# DIY_OpenEVSE_Arduino_Shield.net
KiCad netlist of a schematic drawn in EAGLE
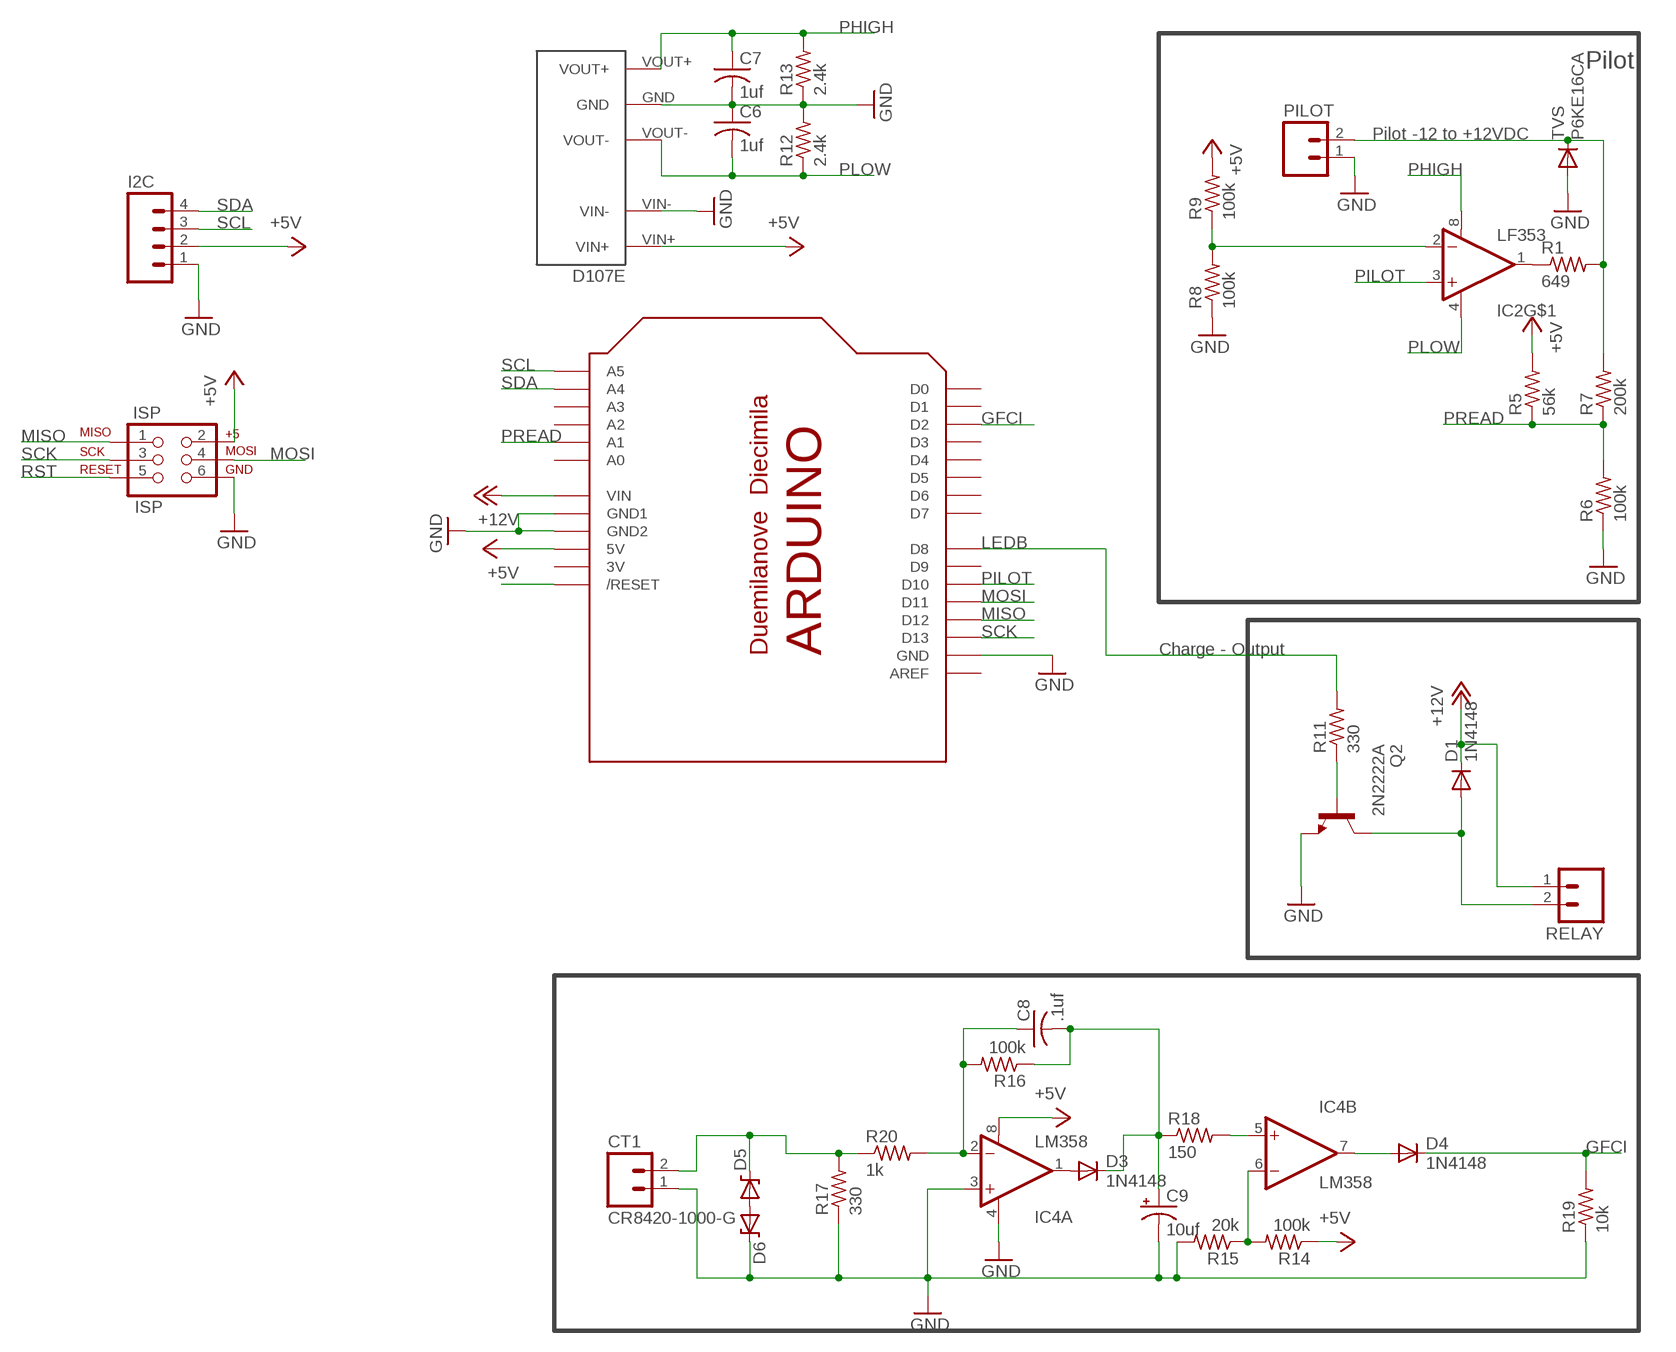
[diagram p0: schematic, sheet 1]

(export (version "E")
  (design (tool "Eeschema 10.0.6"))
  (components
    (comp (ref "C6")
      (value "1uf")
      (footprint "eagle-import:C025-024X044")
      (libsource (lib "eagle-import") (part "C-US025-024X044"))
    )
    (comp (ref "C7")
      (value "1uf")
      (footprint "eagle-import:C025-024X044")
      (libsource (lib "eagle-import") (part "C-US025-024X044"))
    )
    (comp (ref "C8")
      (value ".1uf")
      (footprint "eagle-import:C025-024X044")
      (libsource (lib "eagle-import") (part "C-US025-024X044"))
    )
    (comp (ref "C9")
      (value "10uf")
      (footprint "eagle-import:CPOL-RADIAL-10UF-25V")
      (libsource (lib "eagle-import") (part "CAP_POLPTH2"))
    )
    (comp (ref "CT1")
      (value "CR8420-1000-G")
      (footprint "eagle-import:1X02_LOCK")
      (libsource (lib "eagle-import") (part "M02LOCK"))
    )
    (comp (ref "D1")
      (value "1N4148")
      (footprint "eagle-import:DIODE-1N4148")
      (libsource (lib "eagle-import") (part "DIODE1N4148"))
    )
    (comp (ref "D3")
      (value "1N4148")
      (footprint "eagle-import:DIODE-1N4148")
      (libsource (lib "eagle-import") (part "DIODE1N4148"))
    )
    (comp (ref "D4")
      (value "1N4148")
      (footprint "eagle-import:DIODE-1N4148")
      (libsource (lib "eagle-import") (part "DIODE1N4148"))
    )
    (comp (ref "D5")
      (value "DIODE-ZENERPTH")
      (footprint "eagle-import:DIODE-ZENER")
      (libsource (lib "eagle-import") (part "DIODE-ZENERPTH"))
    )
    (comp (ref "D6")
      (value "DIODE-ZENERPTH")
      (footprint "eagle-import:DIODE-ZENER")
      (libsource (lib "eagle-import") (part "DIODE-ZENERPTH"))
    )
    (comp (ref "I2C")
      (value "M04LOCK")
      (footprint "eagle-import:1X04_LOCK")
      (libsource (lib "eagle-import") (part "M04LOCK"))
    )
    (comp (ref "IC2")
      (value "LF353")
      (footprint "eagle-import:DIP08")
      (libsource (lib "eagle-import") (part "LM358"))
    )
    (comp (ref "IC4")
      (value "LM358")
      (footprint "eagle-import:DIP08")
      (libsource (lib "eagle-import") (part "OPAMP-DUALDIP"))
    )
    (comp (ref "ISP")
      (value "ISP")
      (footprint "eagle-import:2X3_LOCK")
      (libsource (lib "eagle-import") (part "AVR_SPI_PRG_62X3_LOCK"))
    )
    (comp (ref "PILOT")
      (value "M025MM")
      (footprint "eagle-import:SCREWTERMINAL-5MM-2")
      (libsource (lib "eagle-import") (part "M025MM"))
    )
    (comp (ref "Q2")
      (value "2N2222A")
      (footprint "eagle-import:TO18")
      (libsource (lib "eagle-import") (part "2N2222A"))
    )
    (comp (ref "R1")
      (value "649")
      (footprint "eagle-import:0204_7")
      (libsource (lib "eagle-import") (part "R-US_0204/7"))
    )
    (comp (ref "R5")
      (value "56k")
      (footprint "eagle-import:0204_7")
      (libsource (lib "eagle-import") (part "R-US_0204/7"))
    )
    (comp (ref "R6")
      (value "100k")
      (footprint "eagle-import:0204_7")
      (libsource (lib "eagle-import") (part "R-US_0204/7"))
    )
    (comp (ref "R7")
      (value "200k")
      (footprint "eagle-import:0204_7")
      (libsource (lib "eagle-import") (part "R-US_0204/7"))
    )
    (comp (ref "R8")
      (value "100k")
      (footprint "eagle-import:0204_7")
      (libsource (lib "eagle-import") (part "R-US_0204/7"))
    )
    (comp (ref "R9")
      (value "100k")
      (footprint "eagle-import:0204_7")
      (libsource (lib "eagle-import") (part "R-US_0204/7"))
    )
    (comp (ref "R11")
      (value "330")
      (footprint "eagle-import:0204_7")
      (libsource (lib "eagle-import") (part "R-US_0204/7"))
    )
    (comp (ref "R12")
      (value "2.4k")
      (footprint "eagle-import:0204_7")
      (libsource (lib "eagle-import") (part "R-US_0204/7"))
    )
    (comp (ref "R13")
      (value "2.4k")
      (footprint "eagle-import:0204_7")
      (libsource (lib "eagle-import") (part "R-US_0204/7"))
    )
    (comp (ref "R14")
      (value "100k")
      (footprint "eagle-import:0204_7")
      (libsource (lib "eagle-import") (part "R-US_0204/7"))
    )
    (comp (ref "R15")
      (value "20k")
      (footprint "eagle-import:0204_7")
      (libsource (lib "eagle-import") (part "R-US_0204/7"))
    )
    (comp (ref "R16")
      (value "100k")
      (footprint "eagle-import:0204_7")
      (libsource (lib "eagle-import") (part "R-US_0204/7"))
    )
    (comp (ref "R17")
      (value "330")
      (footprint "eagle-import:0204_7")
      (libsource (lib "eagle-import") (part "R-US_0204/7"))
    )
    (comp (ref "R18")
      (value "150")
      (footprint "eagle-import:0204_7")
      (libsource (lib "eagle-import") (part "R-US_0204/7"))
    )
    (comp (ref "R19")
      (value "10k")
      (footprint "eagle-import:0204_7")
      (libsource (lib "eagle-import") (part "R-US_0204/7"))
    )
    (comp (ref "R20")
      (value "1k")
      (footprint "eagle-import:0204_7")
      (libsource (lib "eagle-import") (part "R-US_0204/7"))
    )
    (comp (ref "RELAY")
      (value "M023.5MM_LOCK")
      (footprint "eagle-import:SCREWTERMINAL-3.5MM-2_LOCK")
      (libsource (lib "eagle-import") (part "M023.5MM_LOCK"))
    )
    (comp (ref "TVS")
      (value "P6KE16CA")
      (footprint "eagle-import:DIODE-1N4001")
      (libsource (lib "eagle-import") (part "DIODEPTH"))
    )
    (comp (ref "U$1")
      (value "DCDC_SIP")
      (footprint "eagle-import:DCDC_SIP")
      (libsource (lib "eagle-import") (part "DCDC_SIP"))
    )
    (comp (ref "U$2")
      (value "ARDUINOUNO")
      (footprint "eagle-import:ARDUINO")
      (libsource (lib "eagle-import") (part "ARDUINOUNO"))
    )
  )
  (nets
    (net (code "1") (name "+5V") (class "Default")
      (node (ref "I2C") (pin "2") (pinfunction "2_2") (pintype "passive"))
      (node (ref "IC4") (pin "8") (pinfunction "V+_8") (pintype "power_in"))
      (node (ref "ISP") (pin "2") (pinfunction "2_2") (pintype "passive"))
      (node (ref "R14") (pin "1") (pinfunction "1_1") (pintype "passive"))
      (node (ref "R5") (pin "2") (pinfunction "2_2") (pintype "passive"))
      (node (ref "R9") (pin "2") (pinfunction "2_2") (pintype "passive"))
      (node (ref "U$1") (pin "VIN+") (pinfunction "VIN+_VIN+") (pintype "bidirectional"))
      (node (ref "U$2") (pin "5V") (pinfunction "5V_5V") (pintype "power_in"))
    )
    (net (code "2") (name "+12V") (class "Default")
      (node (ref "D1") (pin "C") (pinfunction "C_C") (pintype "passive"))
      (node (ref "RELAY") (pin "1") (pinfunction "1_1") (pintype "passive"))
      (node (ref "U$2") (pin "VIN") (pinfunction "VIN_VIN") (pintype "power_in"))
    )
    (net (code "3") (name "/3V") (class "Default")
      (node (ref "U$2") (pin "3V") (pinfunction "3V_3V") (pintype "power_in"))
    )
    (net (code "4") (name "/GFCI") (class "Default")
      (node (ref "D4") (pin "C") (pinfunction "C_C") (pintype "passive"))
      (node (ref "R19") (pin "2") (pinfunction "2_2") (pintype "passive"))
      (node (ref "U$2") (pin "D2") (pinfunction "D2_D2") (pintype "bidirectional"))
    )
    (net (code "5") (name "/LEDB") (class "Default")
      (node (ref "R11") (pin "2") (pinfunction "2_2") (pintype "passive"))
      (node (ref "U$2") (pin "D8") (pinfunction "D8_D8") (pintype "bidirectional"))
    )
    (net (code "6") (name "/MISO") (class "Default")
      (node (ref "ISP") (pin "1") (pinfunction "1_1") (pintype "passive"))
      (node (ref "U$2") (pin "D12") (pinfunction "D12_D12") (pintype "bidirectional"))
    )
    (net (code "7") (name "/MOSI") (class "Default")
      (node (ref "ISP") (pin "4") (pinfunction "4_4") (pintype "passive"))
      (node (ref "U$2") (pin "D11") (pinfunction "D11_D11") (pintype "bidirectional"))
    )
    (net (code "8") (name "/PHIGH") (class "Default")
      (node (ref "C7") (pin "1") (pinfunction "1_1") (pintype "passive"))
      (node (ref "IC2") (pin "8") (pinfunction "V+_8") (pintype "power_in"))
      (node (ref "R13") (pin "2") (pinfunction "2_2") (pintype "passive"))
      (node (ref "U$1") (pin "VOUT+") (pinfunction "VOUT+_VOUT+") (pintype "bidirectional"))
    )
    (net (code "9") (name "/PILOT") (class "Default")
      (node (ref "IC2") (pin "3") (pinfunction "+IN_3") (pintype "input"))
      (node (ref "U$2") (pin "D10") (pinfunction "D10_D10") (pintype "bidirectional"))
    )
    (net (code "10") (name "/PLOW") (class "Default")
      (node (ref "C6") (pin "2") (pinfunction "2_2") (pintype "passive"))
      (node (ref "IC2") (pin "4") (pinfunction "V-_4") (pintype "power_in"))
      (node (ref "R12") (pin "1") (pinfunction "1_1") (pintype "passive"))
      (node (ref "U$1") (pin "VOUT-") (pinfunction "VOUT-_VOUT-") (pintype "bidirectional"))
    )
    (net (code "11") (name "/PREAD") (class "Default")
      (node (ref "R5") (pin "1") (pinfunction "1_1") (pintype "passive"))
      (node (ref "R6") (pin "2") (pinfunction "2_2") (pintype "passive"))
      (node (ref "R7") (pin "1") (pinfunction "1_1") (pintype "passive"))
      (node (ref "U$2") (pin "A1") (pinfunction "A1_A1") (pintype "bidirectional"))
    )
    (net (code "12") (name "/RST") (class "Default")
      (node (ref "ISP") (pin "5") (pinfunction "5_5") (pintype "passive"))
      (node (ref "U$2") (pin "RESET") (pinfunction "/RESET_RESET") (pintype "bidirectional"))
    )
    (net (code "13") (name "/SCK") (class "Default")
      (node (ref "ISP") (pin "3") (pinfunction "3_3") (pintype "passive"))
      (node (ref "U$2") (pin "D13") (pinfunction "D13_D13") (pintype "bidirectional"))
    )
    (net (code "14") (name "/SCL") (class "Default")
      (node (ref "I2C") (pin "3") (pinfunction "3_3") (pintype "passive"))
      (node (ref "U$2") (pin "A5") (pinfunction "A5_A5") (pintype "bidirectional"))
    )
    (net (code "15") (name "/SDA") (class "Default")
      (node (ref "I2C") (pin "4") (pinfunction "4_4") (pintype "passive"))
      (node (ref "U$2") (pin "A4") (pinfunction "A4_A4") (pintype "bidirectional"))
    )
    (net (code "16") (name "GND") (class "Default")
      (node (ref "C6") (pin "1") (pinfunction "1_1") (pintype "passive"))
      (node (ref "C7") (pin "2") (pinfunction "2_2") (pintype "passive"))
      (node (ref "C9") (pin "2") (pinfunction "-_2") (pintype "passive"))
      (node (ref "CT1") (pin "1") (pinfunction "1_1") (pintype "passive"))
      (node (ref "D6") (pin "P$1") (pinfunction "C_P$1") (pintype "passive"))
      (node (ref "I2C") (pin "1") (pinfunction "1_1") (pintype "passive"))
      (node (ref "IC4") (pin "3") (pinfunction "+IN_3") (pintype "input"))
      (node (ref "IC4") (pin "4") (pinfunction "V-_4") (pintype "power_in"))
      (node (ref "ISP") (pin "6") (pinfunction "6_6") (pintype "passive"))
      (node (ref "PILOT") (pin "1") (pinfunction "1_1") (pintype "passive"))
      (node (ref "Q2") (pin "1") (pinfunction "E_1") (pintype "passive"))
      (node (ref "R12") (pin "2") (pinfunction "2_2") (pintype "passive"))
      (node (ref "R13") (pin "1") (pinfunction "1_1") (pintype "passive"))
      (node (ref "R15") (pin "2") (pinfunction "2_2") (pintype "passive"))
      (node (ref "R17") (pin "1") (pinfunction "1_1") (pintype "passive"))
      (node (ref "R19") (pin "1") (pinfunction "1_1") (pintype "passive"))
      (node (ref "R6") (pin "1") (pinfunction "1_1") (pintype "passive"))
      (node (ref "R8") (pin "1") (pinfunction "1_1") (pintype "passive"))
      (node (ref "TVS") (pin "A") (pinfunction "A_A") (pintype "passive"))
      (node (ref "U$1") (pin "GND") (pinfunction "GND_GND") (pintype "bidirectional"))
      (node (ref "U$1") (pin "VIN-") (pinfunction "VIN-_VIN-") (pintype "bidirectional"))
      (node (ref "U$2") (pin "GND") (pinfunction "GND_GND") (pintype "power_in"))
      (node (ref "U$2") (pin "GND1") (pinfunction "GND1_GND1") (pintype "power_in"))
      (node (ref "U$2") (pin "GND2") (pinfunction "GND2_GND2") (pintype "power_in"))
    )
    (net (code "17") (name "Net-(C9-+)") (class "Default")
      (node (ref "C8") (pin "2") (pinfunction "2_2") (pintype "passive"))
      (node (ref "C9") (pin "1") (pinfunction "+_1") (pintype "passive"))
      (node (ref "D3") (pin "C") (pinfunction "C_C") (pintype "passive"))
      (node (ref "R16") (pin "1") (pinfunction "1_1") (pintype "passive"))
      (node (ref "R18") (pin "1") (pinfunction "1_1") (pintype "passive"))
    )
    (net (code "18") (name "Net-(D5-A)") (class "Default")
      (node (ref "D5") (pin "P$2") (pinfunction "A_P$2") (pintype "passive"))
      (node (ref "D6") (pin "P$2") (pinfunction "A_P$2") (pintype "passive"))
    )
    (net (code "19") (name "Net-(D5-C)") (class "Default")
      (node (ref "CT1") (pin "2") (pinfunction "2_2") (pintype "passive"))
      (node (ref "D5") (pin "P$1") (pinfunction "C_P$1") (pintype "passive"))
      (node (ref "R17") (pin "2") (pinfunction "2_2") (pintype "passive"))
      (node (ref "R20") (pin "1") (pinfunction "1_1") (pintype "passive"))
    )
    (net (code "20") (name "Net-(IC2A--IN)") (class "Default")
      (node (ref "IC2") (pin "2") (pinfunction "-IN_2") (pintype "input"))
      (node (ref "R8") (pin "2") (pinfunction "2_2") (pintype "passive"))
      (node (ref "R9") (pin "1") (pinfunction "1_1") (pintype "passive"))
    )
    (net (code "21") (name "Net-(IC2A-OUT)") (class "Default")
      (node (ref "IC2") (pin "1") (pinfunction "OUT_1") (pintype "output"))
      (node (ref "R1") (pin "1") (pinfunction "1_1") (pintype "passive"))
    )
    (net (code "22") (name "Net-(IC4A--IN)") (class "Default")
      (node (ref "C8") (pin "1") (pinfunction "1_1") (pintype "passive"))
      (node (ref "IC4") (pin "2") (pinfunction "-IN_2") (pintype "input"))
      (node (ref "R16") (pin "2") (pinfunction "2_2") (pintype "passive"))
      (node (ref "R20") (pin "2") (pinfunction "2_2") (pintype "passive"))
    )
    (net (code "23") (name "Net-(IC4A-OUT)") (class "Default")
      (node (ref "D3") (pin "A") (pinfunction "A_A") (pintype "passive"))
      (node (ref "IC4") (pin "1") (pinfunction "OUT_1") (pintype "output"))
    )
    (net (code "24") (name "Net-(IC4B-+IN)") (class "Default")
      (node (ref "IC4") (pin "5") (pinfunction "+IN_5") (pintype "input"))
      (node (ref "R18") (pin "2") (pinfunction "2_2") (pintype "passive"))
    )
    (net (code "25") (name "Net-(IC4B--IN)") (class "Default")
      (node (ref "IC4") (pin "6") (pinfunction "-IN_6") (pintype "input"))
      (node (ref "R14") (pin "2") (pinfunction "2_2") (pintype "passive"))
      (node (ref "R15") (pin "1") (pinfunction "1_1") (pintype "passive"))
    )
    (net (code "26") (name "Net-(IC4B-OUT)") (class "Default")
      (node (ref "D4") (pin "A") (pinfunction "A_A") (pintype "passive"))
      (node (ref "IC4") (pin "7") (pinfunction "OUT_7") (pintype "output"))
    )
    (net (code "27") (name "Net-(PILOT-Pad2)") (class "Default")
      (node (ref "PILOT") (pin "2") (pinfunction "2_2") (pintype "passive"))
      (node (ref "R1") (pin "2") (pinfunction "2_2") (pintype "passive"))
      (node (ref "R7") (pin "2") (pinfunction "2_2") (pintype "passive"))
      (node (ref "TVS") (pin "C") (pinfunction "C_C") (pintype "passive"))
    )
    (net (code "28") (name "Net-(Q2-B)") (class "Default")
      (node (ref "Q2") (pin "2") (pinfunction "B_2") (pintype "passive"))
      (node (ref "R11") (pin "1") (pinfunction "1_1") (pintype "passive"))
    )
    (net (code "29") (name "Net-(Q2-C)") (class "Default")
      (node (ref "D1") (pin "A") (pinfunction "A_A") (pintype "passive"))
      (node (ref "Q2") (pin "3") (pinfunction "C_3") (pintype "passive"))
      (node (ref "RELAY") (pin "2") (pinfunction "2_2") (pintype "passive"))
    )
    (net (code "30") (name "unconnected-(U$2-PadA0)") (class "Default")
      (node (ref "U$2") (pin "A0") (pinfunction "A0_A0") (pintype "bidirectional"))
    )
    (net (code "31") (name "unconnected-(U$2-PadA2)") (class "Default")
      (node (ref "U$2") (pin "A2") (pinfunction "A2_A2") (pintype "bidirectional"))
    )
    (net (code "32") (name "unconnected-(U$2-PadA3)") (class "Default")
      (node (ref "U$2") (pin "A3") (pinfunction "A3_A3") (pintype "bidirectional"))
    )
    (net (code "33") (name "unconnected-(U$2-PadAREF)") (class "Default")
      (node (ref "U$2") (pin "AREF") (pinfunction "AREF_AREF") (pintype "bidirectional"))
    )
    (net (code "34") (name "unconnected-(U$2-PadD0)") (class "Default")
      (node (ref "U$2") (pin "D0") (pinfunction "D0_D0") (pintype "bidirectional"))
    )
    (net (code "35") (name "unconnected-(U$2-PadD1)") (class "Default")
      (node (ref "U$2") (pin "D1") (pinfunction "D1_D1") (pintype "bidirectional"))
    )
    (net (code "36") (name "unconnected-(U$2-PadD3)") (class "Default")
      (node (ref "U$2") (pin "D3") (pinfunction "D3_D3") (pintype "bidirectional"))
    )
    (net (code "37") (name "unconnected-(U$2-PadD4)") (class "Default")
      (node (ref "U$2") (pin "D4") (pinfunction "D4_D4") (pintype "bidirectional"))
    )
    (net (code "38") (name "unconnected-(U$2-PadD5)") (class "Default")
      (node (ref "U$2") (pin "D5") (pinfunction "D5_D5") (pintype "bidirectional"))
    )
    (net (code "39") (name "unconnected-(U$2-PadD6)") (class "Default")
      (node (ref "U$2") (pin "D6") (pinfunction "D6_D6") (pintype "bidirectional"))
    )
    (net (code "40") (name "unconnected-(U$2-PadD7)") (class "Default")
      (node (ref "U$2") (pin "D7") (pinfunction "D7_D7") (pintype "bidirectional"))
    )
    (net (code "41") (name "unconnected-(U$2-PadD9)") (class "Default")
      (node (ref "U$2") (pin "D9") (pinfunction "D9_D9") (pintype "bidirectional"))
    )
  )
)
